# board_schem_2.net
KiCad netlist of a schematic drawn in EAGLE
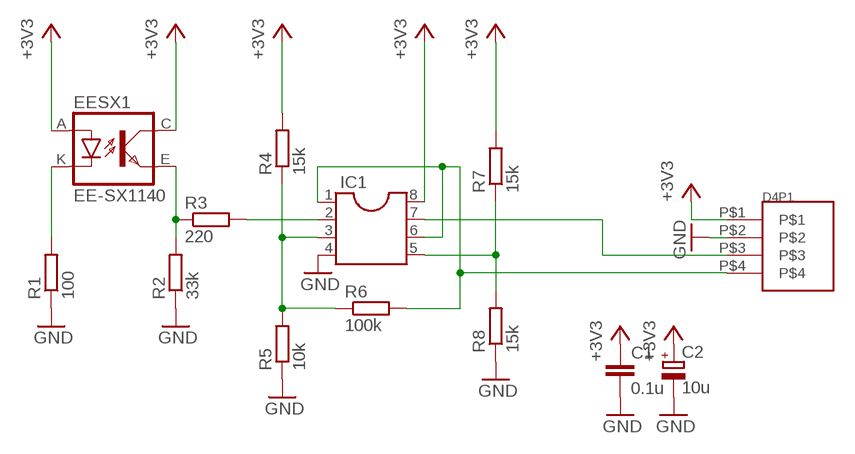
[diagram p0: schematic, sheet 1]

(export (version "E")
  (design (tool "Eeschema 10.0.6"))
  (components
    (comp (ref "C1")
      (value "0.1u")
      (footprint "eagle-import:C050-024X044")
      (libsource (lib "eagle-import") (part "C-EU050-024X044"))
    )
    (comp (ref "C2")
      (value "10u")
      (footprint "eagle-import:E2,5-5")
      (libsource (lib "eagle-import") (part "CPOL-EUE2.5-5"))
    )
    (comp (ref "D4P1")
      (value "DF1E-4P")
      (footprint "eagle-import:DF1E-4P")
      (libsource (lib "eagle-import") (part "DF1E-4P"))
    )
    (comp (ref "EESX1")
      (value "EE-SX1140")
      (footprint "eagle-import:EE-SX1140")
      (libsource (lib "eagle-import") (part "EE-SX1140"))
    )
    (comp (ref "IC1")
      (value "DIL8")
      (footprint "eagle-import:DIL08")
      (libsource (lib "eagle-import") (part "DIL8"))
    )
    (comp (ref "R1")
      (value "100")
      (footprint "eagle-import:0207_10")
      (libsource (lib "eagle-import") (part "R-EU_0207/10"))
    )
    (comp (ref "R2")
      (value "33k")
      (footprint "eagle-import:0207_10")
      (libsource (lib "eagle-import") (part "R-EU_0207/10"))
    )
    (comp (ref "R3")
      (value "220")
      (footprint "eagle-import:0207_10")
      (libsource (lib "eagle-import") (part "R-EU_0207/10"))
    )
    (comp (ref "R4")
      (value "15k")
      (footprint "eagle-import:0207_10")
      (libsource (lib "eagle-import") (part "R-EU_0207/10"))
    )
    (comp (ref "R5")
      (value "10k")
      (footprint "eagle-import:0207_10")
      (libsource (lib "eagle-import") (part "R-EU_0207/10"))
    )
    (comp (ref "R6")
      (value "100k")
      (footprint "eagle-import:0207_10")
      (libsource (lib "eagle-import") (part "R-EU_0207/10"))
    )
    (comp (ref "R7")
      (value "15k")
      (footprint "eagle-import:0207_10")
      (libsource (lib "eagle-import") (part "R-EU_0207/10"))
    )
    (comp (ref "R8")
      (value "15k")
      (footprint "eagle-import:0207_10")
      (libsource (lib "eagle-import") (part "R-EU_0207/10"))
    )
  )
  (nets
    (net (code "1") (name "+3V3") (class "Default")
      (node (ref "C1") (pin "1") (pinfunction "1_1") (pintype "passive"))
      (node (ref "C2") (pin "+") (pinfunction "+_+") (pintype "passive"))
      (node (ref "D4P1") (pin "P$1") (pinfunction "P$1_P$1") (pintype "bidirectional"))
      (node (ref "EESX1") (pin "A") (pinfunction "A_A") (pintype "passive"))
      (node (ref "EESX1") (pin "C") (pinfunction "COL_C") (pintype "passive"))
      (node (ref "IC1") (pin "8") (pinfunction "8_8") (pintype "passive"))
      (node (ref "R4") (pin "2") (pinfunction "2_2") (pintype "passive"))
      (node (ref "R7") (pin "2") (pinfunction "2_2") (pintype "passive"))
    )
    (net (code "2") (name "GND") (class "Default")
      (node (ref "C1") (pin "2") (pinfunction "2_2") (pintype "passive"))
      (node (ref "C2") (pin "-") (pinfunction "-_-") (pintype "passive"))
      (node (ref "D4P1") (pin "P$2") (pinfunction "P$2_P$2") (pintype "bidirectional"))
      (node (ref "IC1") (pin "4") (pinfunction "4_4") (pintype "passive"))
      (node (ref "R1") (pin "1") (pinfunction "1_1") (pintype "passive"))
      (node (ref "R2") (pin "1") (pinfunction "1_1") (pintype "passive"))
      (node (ref "R5") (pin "1") (pinfunction "1_1") (pintype "passive"))
      (node (ref "R8") (pin "1") (pinfunction "1_1") (pintype "passive"))
    )
    (net (code "3") (name "Net-(D4P1-PadP$3)") (class "Default")
      (node (ref "D4P1") (pin "P$3") (pinfunction "P$3_P$3") (pintype "bidirectional"))
      (node (ref "IC1") (pin "7") (pinfunction "7_7") (pintype "passive"))
    )
    (net (code "4") (name "Net-(D4P1-PadP$4)") (class "Default")
      (node (ref "D4P1") (pin "P$4") (pinfunction "P$4_P$4") (pintype "bidirectional"))
      (node (ref "IC1") (pin "1") (pinfunction "1_1") (pintype "passive"))
      (node (ref "IC1") (pin "6") (pinfunction "6_6") (pintype "passive"))
      (node (ref "R6") (pin "2") (pinfunction "2_2") (pintype "passive"))
    )
    (net (code "5") (name "Net-(EESX1-C)") (class "Default")
      (node (ref "EESX1") (pin "K") (pinfunction "C_K") (pintype "passive"))
      (node (ref "R1") (pin "2") (pinfunction "2_2") (pintype "passive"))
    )
    (net (code "6") (name "Net-(EESX1-EMIT)") (class "Default")
      (node (ref "EESX1") (pin "E") (pinfunction "EMIT_E") (pintype "passive"))
      (node (ref "R2") (pin "2") (pinfunction "2_2") (pintype "passive"))
      (node (ref "R3") (pin "1") (pinfunction "1_1") (pintype "passive"))
    )
    (net (code "7") (name "Net-(IC1-Pad2)") (class "Default")
      (node (ref "IC1") (pin "2") (pinfunction "2_2") (pintype "passive"))
      (node (ref "R3") (pin "2") (pinfunction "2_2") (pintype "passive"))
    )
    (net (code "8") (name "Net-(IC1-Pad3)") (class "Default")
      (node (ref "IC1") (pin "3") (pinfunction "3_3") (pintype "passive"))
      (node (ref "R4") (pin "1") (pinfunction "1_1") (pintype "passive"))
      (node (ref "R5") (pin "2") (pinfunction "2_2") (pintype "passive"))
      (node (ref "R6") (pin "1") (pinfunction "1_1") (pintype "passive"))
    )
    (net (code "9") (name "Net-(IC1-Pad5)") (class "Default")
      (node (ref "IC1") (pin "5") (pinfunction "5_5") (pintype "passive"))
      (node (ref "R7") (pin "1") (pinfunction "1_1") (pintype "passive"))
      (node (ref "R8") (pin "2") (pinfunction "2_2") (pintype "passive"))
    )
  )
)
